# flow_7s_wo_uart_manual.net
KiCad netlist of a schematic drawn in EAGLE
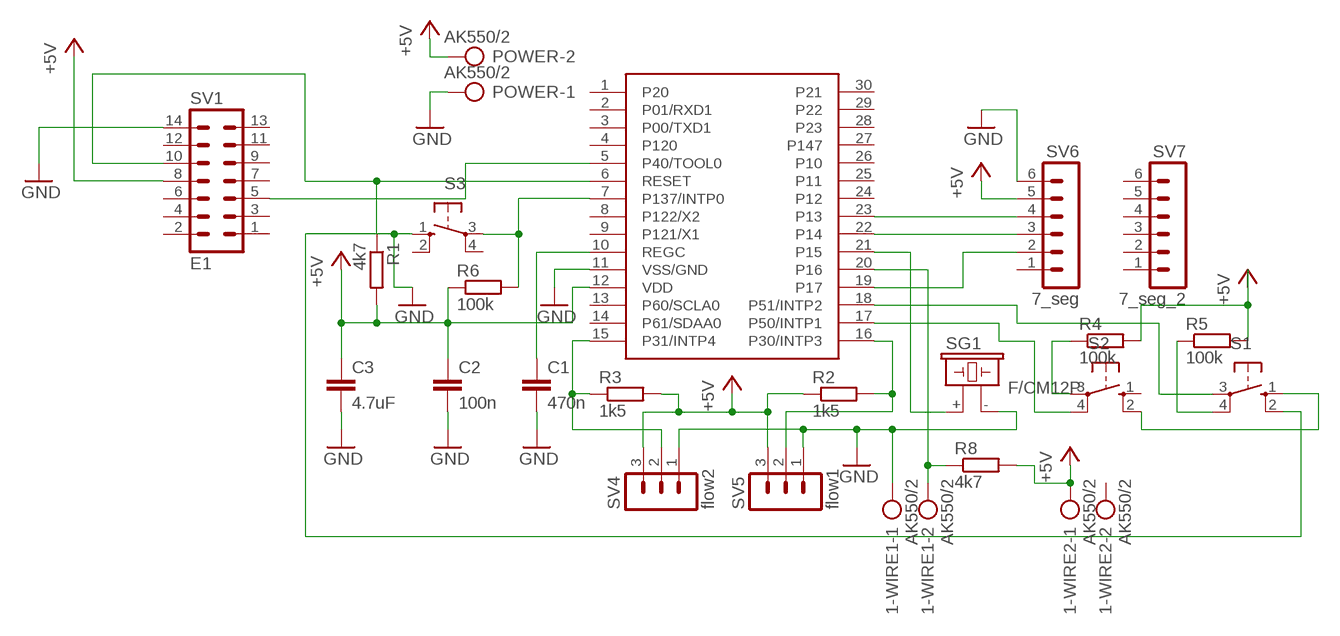
[diagram p0: schematic, sheet 1]

(export (version "E")
  (design (tool "Eeschema 10.0.6"))
  (components
    (comp (ref "1-WIRE1")
      (value "AK550/2")
      (footprint "eagle-import:AK550_2")
      (libsource (lib "eagle-import") (part "AK550/2"))
    )
    (comp (ref "1-WIRE2")
      (value "AK550/2")
      (footprint "eagle-import:AK550_2")
      (libsource (lib "eagle-import") (part "AK550/2"))
    )
    (comp (ref "C1")
      (value "470n")
      (footprint "eagle-import:C1206")
      (libsource (lib "eagle-import") (part "C-EUC1206"))
    )
    (comp (ref "C2")
      (value "100n")
      (footprint "eagle-import:C1206")
      (libsource (lib "eagle-import") (part "C-EUC1206"))
    )
    (comp (ref "C3")
      (value "4.7uF")
      (footprint "eagle-import:C1206")
      (libsource (lib "eagle-import") (part "C-EUC1206"))
    )
    (comp (ref "POWER")
      (value "AK550/2")
      (footprint "eagle-import:AK550_2")
      (libsource (lib "eagle-import") (part "AK550/2"))
    )
    (comp (ref "R1")
      (value "4k7")
      (footprint "eagle-import:R1206")
      (libsource (lib "eagle-import") (part "R-EU_R1206"))
    )
    (comp (ref "R2")
      (value "1k5")
      (footprint "eagle-import:R1206")
      (libsource (lib "eagle-import") (part "R-EU_R1206"))
    )
    (comp (ref "R3")
      (value "1k5")
      (footprint "eagle-import:R1206")
      (libsource (lib "eagle-import") (part "R-EU_R1206"))
    )
    (comp (ref "R4")
      (value "100k")
      (footprint "eagle-import:R1206")
      (libsource (lib "eagle-import") (part "R-EU_R1206"))
    )
    (comp (ref "R5")
      (value "100k")
      (footprint "eagle-import:R1206")
      (libsource (lib "eagle-import") (part "R-EU_R1206"))
    )
    (comp (ref "R6")
      (value "100k")
      (footprint "eagle-import:R1206")
      (libsource (lib "eagle-import") (part "R-EU_R1206"))
    )
    (comp (ref "R8")
      (value "4k7")
      (footprint "eagle-import:R1206")
      (libsource (lib "eagle-import") (part "R-EU_R1206"))
    )
    (comp (ref "S1")
      (value "10-XX")
      (footprint "eagle-import:B3F-10XX")
      (fields (field (name "MPN") "B3F-1000"))
      (libsource (lib "eagle-import") (part "10-XX"))
    )
    (comp (ref "S2")
      (value "10-XX")
      (footprint "eagle-import:B3F-10XX")
      (fields (field (name "MPN") "B3F-1000"))
      (libsource (lib "eagle-import") (part "10-XX"))
    )
    (comp (ref "S3")
      (value "10-XX")
      (footprint "eagle-import:B3F-10XX")
      (fields (field (name "MPN") "B3F-1000"))
      (libsource (lib "eagle-import") (part "10-XX"))
    )
    (comp (ref "SG1")
      (value "F/CM12P")
      (footprint "eagle-import:F_CM12P")
      (libsource (lib "eagle-import") (part "F/CM12P"))
    )
    (comp (ref "SV1")
      (value "E1")
      (footprint "eagle-import:MA07-2")
      (libsource (lib "eagle-import") (part "MA07-2"))
    )
    (comp (ref "SV4")
      (value "flow2")
      (footprint "eagle-import:MA03-1")
      (libsource (lib "eagle-import") (part "MA03-1"))
    )
    (comp (ref "SV5")
      (value "flow1")
      (footprint "eagle-import:MA03-1")
      (libsource (lib "eagle-import") (part "MA03-1"))
    )
    (comp (ref "SV6")
      (value "7_seg")
      (footprint "eagle-import:MA06-1")
      (libsource (lib "eagle-import") (part "MA06-1"))
    )
    (comp (ref "SV7")
      (value "7_seg_2")
      (footprint "eagle-import:MA06-1")
      (libsource (lib "eagle-import") (part "MA06-1"))
    )
    (comp (ref "U$1")
      (value "R5F100A")
      (footprint "eagle-import:SSOP30")
      (libsource (lib "eagle-import") (part "R5F100A"))
    )
  )
  (nets
    (net (code "1") (name "+5V") (class "Default")
      (node (ref "1-WIRE2") (pin "1") (pinfunction "KL_1") (pintype "passive"))
      (node (ref "C2") (pin "1") (pinfunction "1_1") (pintype "passive"))
      (node (ref "C3") (pin "1") (pinfunction "1_1") (pintype "passive"))
      (node (ref "POWER") (pin "2") (pinfunction "KL_2") (pintype "passive"))
      (node (ref "R1") (pin "2") (pinfunction "2_2") (pintype "passive"))
      (node (ref "R2") (pin "1") (pinfunction "1_1") (pintype "passive"))
      (node (ref "R3") (pin "2") (pinfunction "2_2") (pintype "passive"))
      (node (ref "R4") (pin "2") (pinfunction "2_2") (pintype "passive"))
      (node (ref "R5") (pin "2") (pinfunction "2_2") (pintype "passive"))
      (node (ref "R6") (pin "1") (pinfunction "1_1") (pintype "passive"))
      (node (ref "R8") (pin "2") (pinfunction "2_2") (pintype "passive"))
      (node (ref "SV1") (pin "8") (pinfunction "8_8") (pintype "passive"))
      (node (ref "SV4") (pin "3") (pinfunction "3_3") (pintype "passive"))
      (node (ref "SV5") (pin "3") (pinfunction "3_3") (pintype "passive"))
      (node (ref "SV6") (pin "5") (pinfunction "5_5") (pintype "passive"))
      (node (ref "U$1") (pin "12") (pinfunction "VDD_12") (pintype "bidirectional"))
    )
    (net (code "2") (name "GND") (class "Default")
      (node (ref "1-WIRE1") (pin "1") (pinfunction "KL_1") (pintype "passive"))
      (node (ref "C1") (pin "2") (pinfunction "2_2") (pintype "passive"))
      (node (ref "C2") (pin "2") (pinfunction "2_2") (pintype "passive"))
      (node (ref "C3") (pin "2") (pinfunction "2_2") (pintype "passive"))
      (node (ref "POWER") (pin "1") (pinfunction "KL_1") (pintype "passive"))
      (node (ref "S1") (pin "2") (pinfunction "S1_2") (pintype "passive"))
      (node (ref "S3") (pin "1") (pinfunction "S_1") (pintype "passive"))
      (node (ref "SG1") (pin "-") (pinfunction "2_-") (pintype "passive"))
      (node (ref "SV1") (pin "14") (pinfunction "14_14") (pintype "passive"))
      (node (ref "SV4") (pin "1") (pinfunction "1_1") (pintype "passive"))
      (node (ref "SV5") (pin "1") (pinfunction "1_1") (pintype "passive"))
      (node (ref "SV6") (pin "6") (pinfunction "6_6") (pintype "passive"))
      (node (ref "U$1") (pin "11") (pinfunction "VSS/GND_11") (pintype "bidirectional"))
    )
    (net (code "3") (name "Net-(1-WIRE1B-KL)") (class "Default")
      (node (ref "1-WIRE1") (pin "2") (pinfunction "KL_2") (pintype "passive"))
      (node (ref "R8") (pin "1") (pinfunction "1_1") (pintype "passive"))
      (node (ref "U$1") (pin "20") (pinfunction "P16_20") (pintype "bidirectional"))
    )
    (net (code "4") (name "Net-(S1-P)") (class "Default")
      (node (ref "S1") (pin "3") (pinfunction "P_3") (pintype "passive"))
      (node (ref "U$1") (pin "18") (pinfunction "P51/INTP2_18") (pintype "bidirectional"))
    )
    (net (code "5") (name "Net-(S1-P1)") (class "Default")
      (node (ref "R5") (pin "1") (pinfunction "1_1") (pintype "passive"))
      (node (ref "S1") (pin "4") (pinfunction "P1_4") (pintype "passive"))
    )
    (net (code "6") (name "Net-(S1-S)") (class "Default")
      (node (ref "S1") (pin "1") (pinfunction "S_1") (pintype "passive"))
      (node (ref "S2") (pin "2") (pinfunction "S1_2") (pintype "passive"))
    )
    (net (code "7") (name "Net-(S2-P)") (class "Default")
      (node (ref "R4") (pin "1") (pinfunction "1_1") (pintype "passive"))
      (node (ref "S2") (pin "3") (pinfunction "P_3") (pintype "passive"))
    )
    (net (code "8") (name "Net-(S2-P1)") (class "Default")
      (node (ref "S2") (pin "4") (pinfunction "P1_4") (pintype "passive"))
      (node (ref "U$1") (pin "17") (pinfunction "P50/INTP1_17") (pintype "bidirectional"))
    )
    (net (code "9") (name "Net-(S3-P)") (class "Default")
      (node (ref "R6") (pin "2") (pinfunction "2_2") (pintype "passive"))
      (node (ref "S3") (pin "3") (pinfunction "P_3") (pintype "passive"))
      (node (ref "U$1") (pin "7") (pinfunction "P137/INTP0_7") (pintype "bidirectional"))
    )
    (net (code "10") (name "Net-(SG1-1)") (class "Default")
      (node (ref "SG1") (pin "+") (pinfunction "1_+") (pintype "passive"))
      (node (ref "U$1") (pin "21") (pinfunction "P15_21") (pintype "bidirectional"))
    )
    (net (code "11") (name "Net-(U$1-P13)") (class "Default")
      (node (ref "SV6") (pin "4") (pinfunction "4_4") (pintype "passive"))
      (node (ref "U$1") (pin "23") (pinfunction "P13_23") (pintype "bidirectional"))
    )
    (net (code "12") (name "Net-(U$1-P14)") (class "Default")
      (node (ref "SV6") (pin "3") (pinfunction "3_3") (pintype "passive"))
      (node (ref "U$1") (pin "22") (pinfunction "P14_22") (pintype "bidirectional"))
    )
    (net (code "13") (name "Net-(U$1-P17)") (class "Default")
      (node (ref "SV6") (pin "2") (pinfunction "2_2") (pintype "passive"))
      (node (ref "U$1") (pin "19") (pinfunction "P17_19") (pintype "bidirectional"))
    )
    (net (code "14") (name "Net-(U$1-P30{slash}INTP3)") (class "Default")
      (node (ref "R2") (pin "2") (pinfunction "2_2") (pintype "passive"))
      (node (ref "SV5") (pin "2") (pinfunction "2_2") (pintype "passive"))
      (node (ref "U$1") (pin "16") (pinfunction "P30/INTP3_16") (pintype "bidirectional"))
    )
    (net (code "15") (name "Net-(U$1-P31{slash}INTP4)") (class "Default")
      (node (ref "R3") (pin "1") (pinfunction "1_1") (pintype "passive"))
      (node (ref "SV4") (pin "2") (pinfunction "2_2") (pintype "passive"))
      (node (ref "U$1") (pin "15") (pinfunction "P31/INTP4_15") (pintype "bidirectional"))
    )
    (net (code "16") (name "Net-(U$1-P40{slash}TOOL0)") (class "Default")
      (node (ref "SV1") (pin "5") (pinfunction "5_5") (pintype "passive"))
      (node (ref "U$1") (pin "5") (pinfunction "P40/TOOL0_5") (pintype "bidirectional"))
    )
    (net (code "17") (name "Net-(U$1-REGC)") (class "Default")
      (node (ref "C1") (pin "1") (pinfunction "1_1") (pintype "passive"))
      (node (ref "U$1") (pin "10") (pinfunction "REGC_10") (pintype "bidirectional"))
    )
    (net (code "18") (name "Net-(U$1-RESET)") (class "Default")
      (node (ref "R1") (pin "1") (pinfunction "1_1") (pintype "passive"))
      (node (ref "SV1") (pin "10") (pinfunction "10_10") (pintype "passive"))
      (node (ref "U$1") (pin "6") (pinfunction "RESET_6") (pintype "bidirectional"))
    )
    (net (code "19") (name "unconnected-(1-WIRE2B-KL-Pad2)") (class "Default")
      (node (ref "1-WIRE2") (pin "2") (pinfunction "KL_2") (pintype "passive"))
    )
    (net (code "20") (name "unconnected-(S2-S-Pad1)") (class "Default")
      (node (ref "S2") (pin "1") (pinfunction "S_1") (pintype "passive"))
    )
    (net (code "21") (name "unconnected-(S3-P1-Pad4)") (class "Default")
      (node (ref "S3") (pin "4") (pinfunction "P1_4") (pintype "passive"))
    )
    (net (code "22") (name "unconnected-(S3-S1-Pad2)") (class "Default")
      (node (ref "S3") (pin "2") (pinfunction "S1_2") (pintype "passive"))
    )
    (net (code "23") (name "unconnected-(SV1-Pad1)") (class "Default")
      (node (ref "SV1") (pin "1") (pinfunction "1_1") (pintype "passive"))
    )
    (net (code "24") (name "unconnected-(SV1-Pad2)") (class "Default")
      (node (ref "SV1") (pin "2") (pinfunction "2_2") (pintype "passive"))
    )
    (net (code "25") (name "unconnected-(SV1-Pad3)") (class "Default")
      (node (ref "SV1") (pin "3") (pinfunction "3_3") (pintype "passive"))
    )
    (net (code "26") (name "unconnected-(SV1-Pad4)") (class "Default")
      (node (ref "SV1") (pin "4") (pinfunction "4_4") (pintype "passive"))
    )
    (net (code "27") (name "unconnected-(SV1-Pad6)") (class "Default")
      (node (ref "SV1") (pin "6") (pinfunction "6_6") (pintype "passive"))
    )
    (net (code "28") (name "unconnected-(SV1-Pad7)") (class "Default")
      (node (ref "SV1") (pin "7") (pinfunction "7_7") (pintype "passive"))
    )
    (net (code "29") (name "unconnected-(SV1-Pad9)") (class "Default")
      (node (ref "SV1") (pin "9") (pinfunction "9_9") (pintype "passive"))
    )
    (net (code "30") (name "unconnected-(SV1-Pad11)") (class "Default")
      (node (ref "SV1") (pin "11") (pinfunction "11_11") (pintype "passive"))
    )
    (net (code "31") (name "unconnected-(SV1-Pad12)") (class "Default")
      (node (ref "SV1") (pin "12") (pinfunction "12_12") (pintype "passive"))
    )
    (net (code "32") (name "unconnected-(SV1-Pad13)") (class "Default")
      (node (ref "SV1") (pin "13") (pinfunction "13_13") (pintype "passive"))
    )
    (net (code "33") (name "unconnected-(SV6-Pad1)") (class "Default")
      (node (ref "SV6") (pin "1") (pinfunction "1_1") (pintype "passive"))
    )
    (net (code "34") (name "unconnected-(SV7-Pad1)") (class "Default")
      (node (ref "SV7") (pin "1") (pinfunction "1_1") (pintype "passive"))
    )
    (net (code "35") (name "unconnected-(SV7-Pad2)") (class "Default")
      (node (ref "SV7") (pin "2") (pinfunction "2_2") (pintype "passive"))
    )
    (net (code "36") (name "unconnected-(SV7-Pad3)") (class "Default")
      (node (ref "SV7") (pin "3") (pinfunction "3_3") (pintype "passive"))
    )
    (net (code "37") (name "unconnected-(SV7-Pad4)") (class "Default")
      (node (ref "SV7") (pin "4") (pinfunction "4_4") (pintype "passive"))
    )
    (net (code "38") (name "unconnected-(SV7-Pad5)") (class "Default")
      (node (ref "SV7") (pin "5") (pinfunction "5_5") (pintype "passive"))
    )
    (net (code "39") (name "unconnected-(SV7-Pad6)") (class "Default")
      (node (ref "SV7") (pin "6") (pinfunction "6_6") (pintype "passive"))
    )
    (net (code "40") (name "unconnected-(U$1-P00{slash}TXD1-Pad3)") (class "Default")
      (node (ref "U$1") (pin "3") (pinfunction "P00/TXD1_3") (pintype "bidirectional"))
    )
    (net (code "41") (name "unconnected-(U$1-P01{slash}RXD1-Pad2)") (class "Default")
      (node (ref "U$1") (pin "2") (pinfunction "P01/RXD1_2") (pintype "bidirectional"))
    )
    (net (code "42") (name "unconnected-(U$1-P10-Pad26)") (class "Default")
      (node (ref "U$1") (pin "26") (pinfunction "P10_26") (pintype "bidirectional"))
    )
    (net (code "43") (name "unconnected-(U$1-P11-Pad25)") (class "Default")
      (node (ref "U$1") (pin "25") (pinfunction "P11_25") (pintype "bidirectional"))
    )
    (net (code "44") (name "unconnected-(U$1-P12-Pad24)") (class "Default")
      (node (ref "U$1") (pin "24") (pinfunction "P12_24") (pintype "bidirectional"))
    )
    (net (code "45") (name "unconnected-(U$1-P20-Pad1)") (class "Default")
      (node (ref "U$1") (pin "1") (pinfunction "P20_1") (pintype "bidirectional"))
    )
    (net (code "46") (name "unconnected-(U$1-P21-Pad30)") (class "Default")
      (node (ref "U$1") (pin "30") (pinfunction "P21_30") (pintype "bidirectional"))
    )
    (net (code "47") (name "unconnected-(U$1-P22-Pad29)") (class "Default")
      (node (ref "U$1") (pin "29") (pinfunction "P22_29") (pintype "bidirectional"))
    )
    (net (code "48") (name "unconnected-(U$1-P23-Pad28)") (class "Default")
      (node (ref "U$1") (pin "28") (pinfunction "P23_28") (pintype "bidirectional"))
    )
    (net (code "49") (name "unconnected-(U$1-P60{slash}SCLA0-Pad13)") (class "Default")
      (node (ref "U$1") (pin "13") (pinfunction "P60/SCLA0_13") (pintype "bidirectional"))
    )
    (net (code "50") (name "unconnected-(U$1-P61{slash}SDAA0-Pad14)") (class "Default")
      (node (ref "U$1") (pin "14") (pinfunction "P61/SDAA0_14") (pintype "bidirectional"))
    )
    (net (code "51") (name "unconnected-(U$1-P120-Pad4)") (class "Default")
      (node (ref "U$1") (pin "4") (pinfunction "P120_4") (pintype "bidirectional"))
    )
    (net (code "52") (name "unconnected-(U$1-P121{slash}X1-Pad9)") (class "Default")
      (node (ref "U$1") (pin "9") (pinfunction "P121/X1_9") (pintype "bidirectional"))
    )
    (net (code "53") (name "unconnected-(U$1-P122{slash}X2-Pad8)") (class "Default")
      (node (ref "U$1") (pin "8") (pinfunction "P122/X2_8") (pintype "bidirectional"))
    )
    (net (code "54") (name "unconnected-(U$1-P147-Pad27)") (class "Default")
      (node (ref "U$1") (pin "27") (pinfunction "P147_27") (pintype "bidirectional"))
    )
  )
)
